# Sensor_Signal.net
KiCad netlist of a schematic drawn in Altium Designer
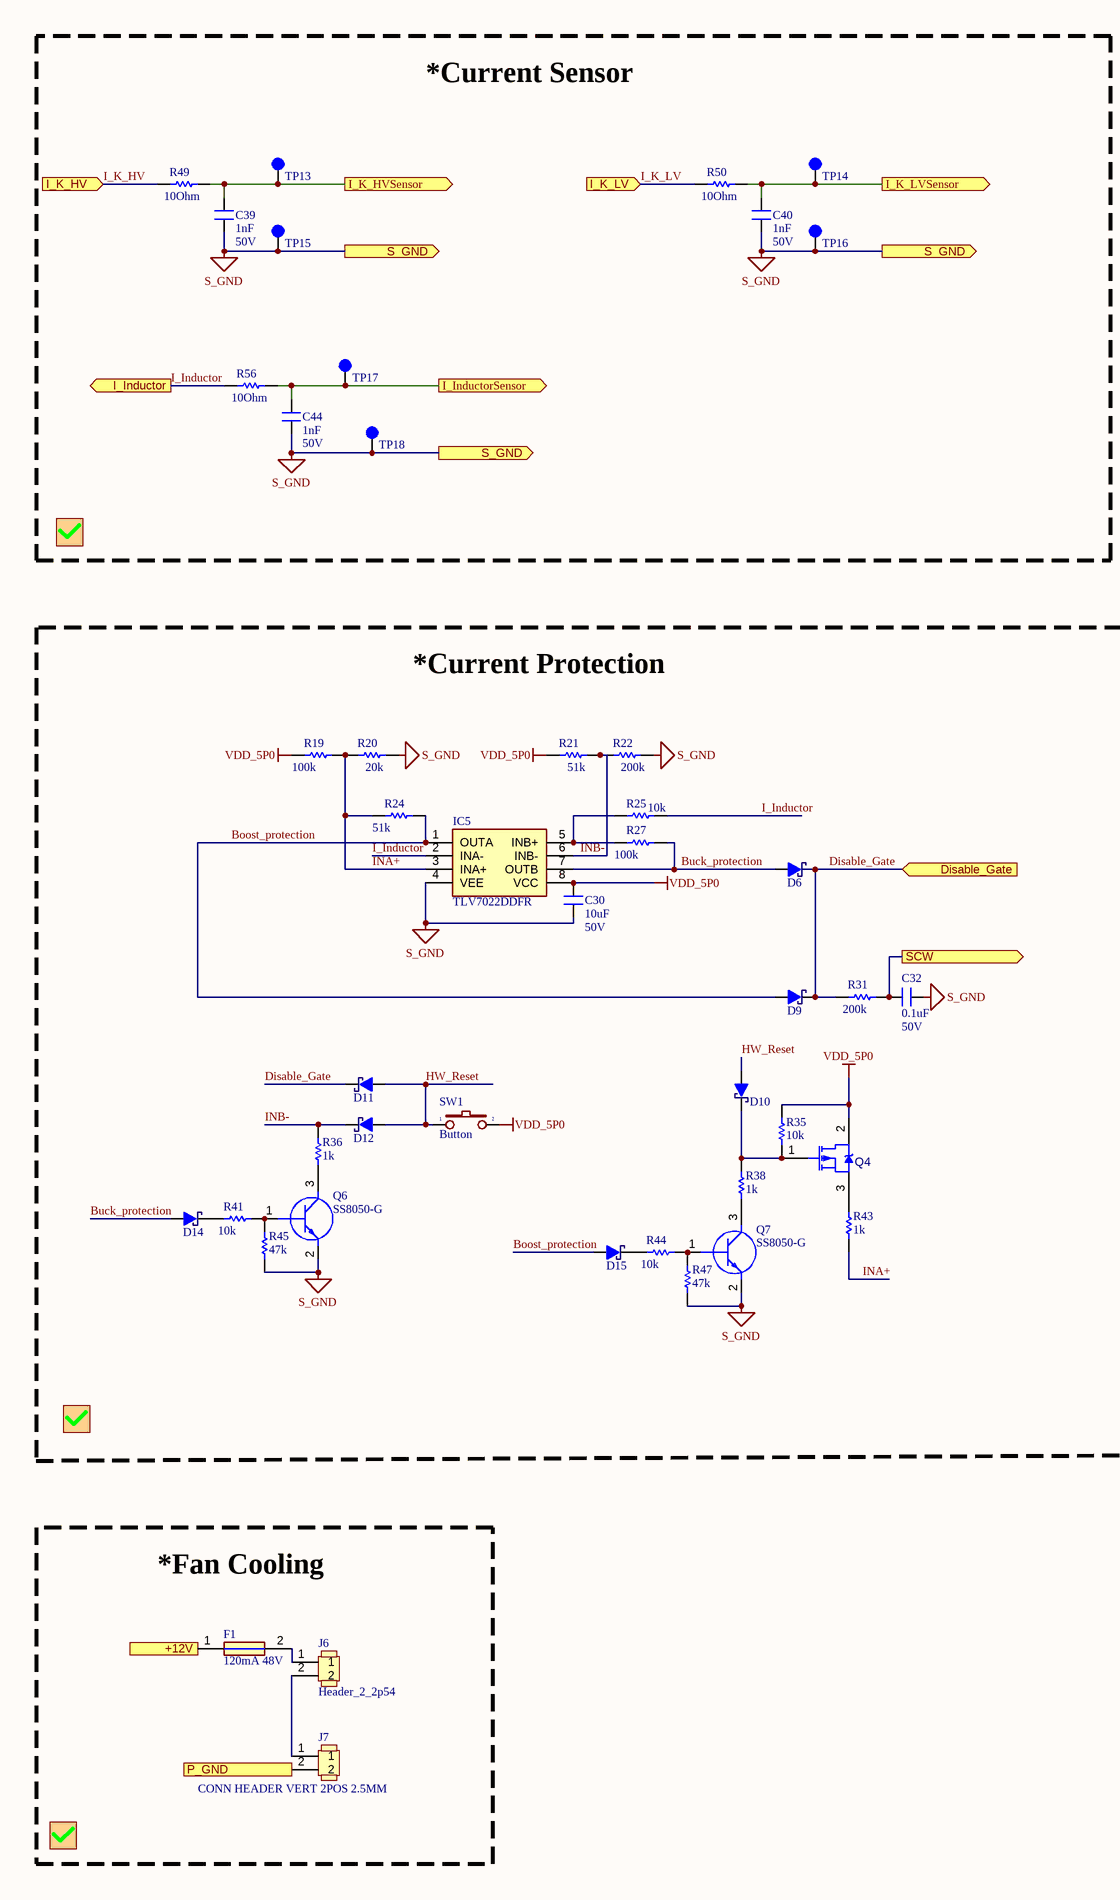
[diagram p0: Sensor Signal.SchDoc, left]
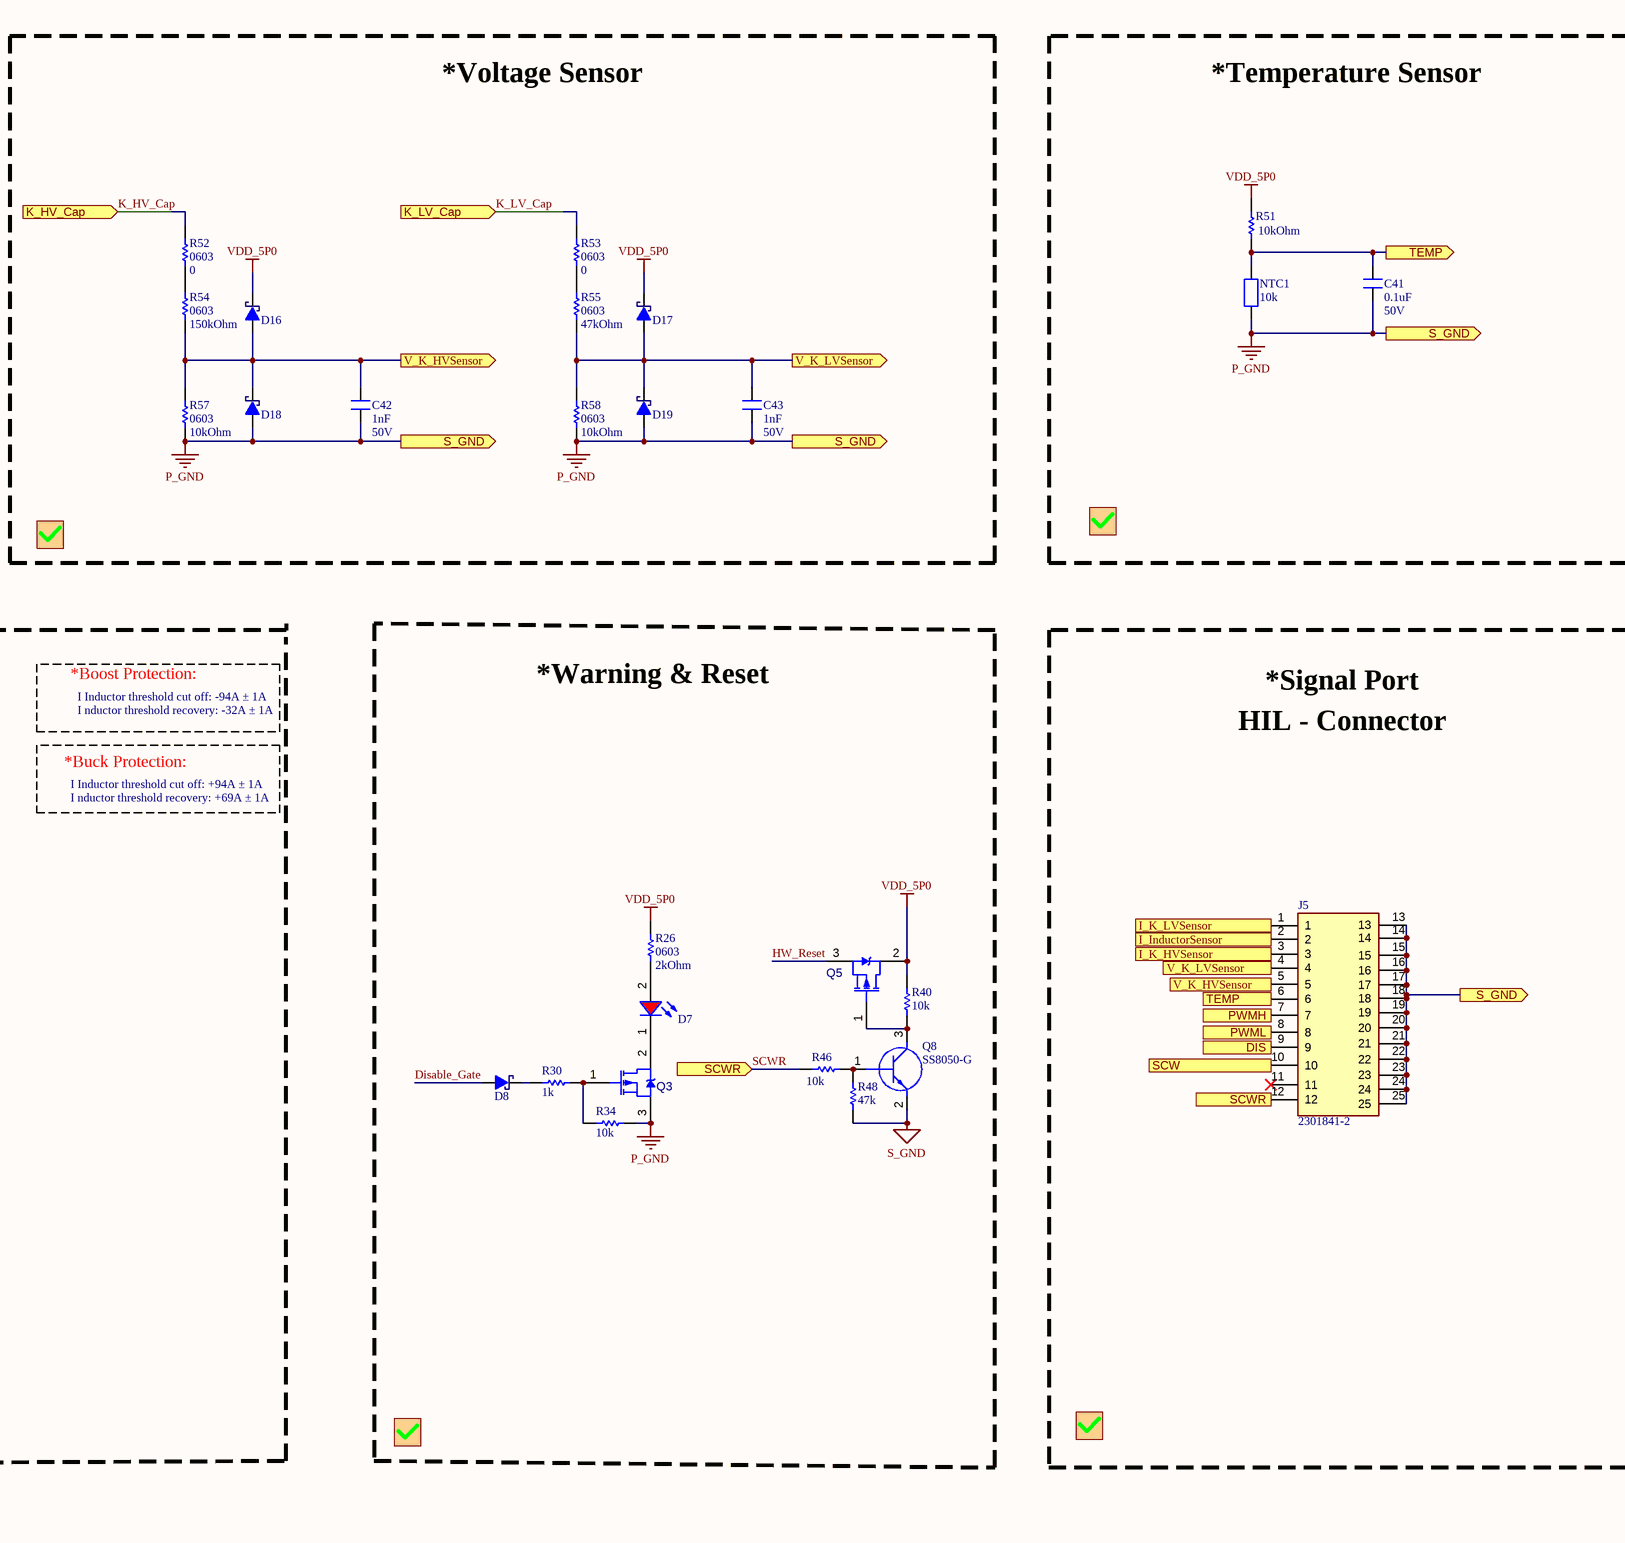
[diagram p1: Sensor Signal.SchDoc, right]

(export (version "E")
  (design (tool "Eeschema 10.0.6"))
  (components
    (comp (ref "C30")
      (value "10uF")
      (footprint "C_0603")
      (description "CAP CER 10UF 16V X5R 0805")
      (fields
        (field (name "MANUFACTURER") "Murata Electronics")
        (field (name "PART NUMBER") "CL21A106KOCLRNC")
        (field (name "ALTIUM_VALUE") "50V")
      )
      (libsource (lib "S1200_Capacitor") (part "Cap_Cer_0603_1nF_25V"))
    )
    (comp (ref "C32")
      (value "0.1uF")
      (footprint "C_0603")
      (description "CAP CER 0.1UF 16V X5R 0603")
      (fields
        (field (name "MANUFACTURER") "Murata Electronics")
        (field (name "PART NUMBER") "CL21A106KOCLRNC")
        (field (name "ALTIUM_VALUE") "50V")
      )
      (libsource (lib "S1200_Capacitor") (part "Cap_Cer_0603_1nF_25V"))
    )
    (comp (ref "C39")
      (value "1nF")
      (footprint "C_0603")
      (description "CAP CER 1nF 50V X7R 0603")
      (fields
        (field (name "MANUFACTURER") "Murata Electronics")
        (field (name "PART NUMBER") "GCM188R71E102KA37D")
        (field (name "ALTIUM_VALUE") "50V")
      )
      (libsource (lib "S1200_Capacitor") (part "Cap_Cer_0603_1nF_25V"))
    )
    (comp (ref "C40")
      (value "1nF")
      (footprint "C_0603")
      (description "CAP CER 1nF 50V X7R 0603")
      (fields
        (field (name "MANUFACTURER") "Murata Electronics")
        (field (name "PART NUMBER") "GCM188R71E102KA37D")
        (field (name "ALTIUM_VALUE") "50V")
      )
      (libsource (lib "S1200_Capacitor") (part "Cap_Cer_0603_1nF_25V"))
    )
    (comp (ref "C41")
      (value "0.1uF")
      (footprint "C_0603")
      (description "CAP CER 0.1uF 50V X7R 0603")
      (fields
        (field (name "MANUFACTURER") "Kemet")
        (field (name "PART NUMBER") "CL10C680JB81PNC")
        (field (name "ALTIUM_VALUE") "50V")
      )
      (libsource (lib "S1200_Capacitor") (part "Cap_Cer_0805_10pF"))
    )
    (comp (ref "C42")
      (value "1nF")
      (footprint "C_0603")
      (description "CAP CER 1nF 50V X7R 0603")
      (fields
        (field (name "MANUFACTURER") "Murata Electronics")
        (field (name "PART NUMBER") "GCM188R71E102KA37D")
        (field (name "ALTIUM_VALUE") "50V")
      )
      (libsource (lib "S1200_Capacitor") (part "Cap_Cer_0603_1nF_25V"))
    )
    (comp (ref "C43")
      (value "1nF")
      (footprint "C_0603")
      (description "CAP CER 1nF 50V X7R 0603")
      (fields
        (field (name "MANUFACTURER") "Murata Electronics")
        (field (name "PART NUMBER") "GCM188R71E102KA37D")
        (field (name "ALTIUM_VALUE") "50V")
      )
      (libsource (lib "S1200_Capacitor") (part "Cap_Cer_0603_1nF_25V"))
    )
    (comp (ref "C44")
      (value "1nF")
      (footprint "C_0603")
      (description "CAP CER 1nF 50V X7R 0603")
      (fields
        (field (name "MANUFACTURER") "Murata Electronics")
        (field (name "PART NUMBER") "GCM188R71E102KA37D")
        (field (name "ALTIUM_VALUE") "50V")
      )
      (libsource (lib "S1200_Capacitor") (part "Cap_Cer_0603_1nF_25V"))
    )
    (comp (ref "D6")
      (value "PMEG2010AEJ,115")
      (footprint "SOD323F")
      (description "DIODE SCHOTTKY 20V 1A SOD323F")
      (fields (field (name "MANUFACTURER") "Nexperia USA Inc.") (field (name "VOLTAGE") "20 V"))
      (libsource (lib "Motor Control SELEX MOTORS JSC") (part "PMEG2010AEJ,115"))
    )
    (comp (ref "D7")
      (value "LED-SMD")
      (footprint "SM-LED-0805-Red")
      (description "LED RED DIFFUSED 0805 SMD")
      (fields
        (field (name "MANUFACTURER") "OSRAM Opto Semiconductors Inc.")
        (field (name "PART NUMBER") "LS R976-NR-1")
      )
      (libsource (lib "Motor Control SELEX MOTORS JSC") (part "LED-SMD"))
    )
    (comp (ref "D8")
      (value "PMEG2010AEJ,115")
      (footprint "SOD323F")
      (description "DIODE SCHOTTKY 20V 1A SOD323F")
      (fields (field (name "MANUFACTURER") "Nexperia USA Inc.") (field (name "VOLTAGE") "20 V"))
      (libsource (lib "Motor Control SELEX MOTORS JSC") (part "PMEG2010AEJ,115"))
    )
    (comp (ref "D9")
      (value "PMEG2010AEJ,115")
      (footprint "SOD323F")
      (description "DIODE SCHOTTKY 20V 1A SOD323F")
      (fields (field (name "MANUFACTURER") "Nexperia USA Inc.") (field (name "VOLTAGE") "20 V"))
      (libsource (lib "Motor Control SELEX MOTORS JSC") (part "PMEG2010AEJ,115"))
    )
    (comp (ref "D10")
      (value "PMEG2010AEJ,115")
      (footprint "SOD323F")
      (description "DIODE SCHOTTKY 20V 1A SOD323F")
      (fields (field (name "MANUFACTURER") "Nexperia USA Inc.") (field (name "VOLTAGE") "20 V"))
      (libsource (lib "Motor Control SELEX MOTORS JSC") (part "PMEG2010AEJ,115"))
    )
    (comp (ref "D11")
      (value "PMEG2010AEJ,115")
      (footprint "SOD323F")
      (description "DIODE SCHOTTKY 20V 1A SOD323F")
      (fields (field (name "MANUFACTURER") "Nexperia USA Inc.") (field (name "VOLTAGE") "20 V"))
      (libsource (lib "Motor Control SELEX MOTORS JSC") (part "PMEG2010AEJ,115"))
    )
    (comp (ref "D12")
      (value "PMEG2010AEJ,115")
      (footprint "SOD323F")
      (description "DIODE SCHOTTKY 20V 1A SOD323F")
      (fields (field (name "MANUFACTURER") "Nexperia USA Inc.") (field (name "VOLTAGE") "20 V"))
      (libsource (lib "Motor Control SELEX MOTORS JSC") (part "PMEG2010AEJ,115"))
    )
    (comp (ref "D14")
      (value "PMEG2010AEJ,115")
      (footprint "SOD323F")
      (description "DIODE SCHOTTKY 20V 1A SOD323F")
      (fields (field (name "MANUFACTURER") "Nexperia USA Inc.") (field (name "VOLTAGE") "20 V"))
      (libsource (lib "Motor Control SELEX MOTORS JSC") (part "PMEG2010AEJ,115"))
    )
    (comp (ref "D15")
      (value "PMEG2010AEJ,115")
      (footprint "SOD323F")
      (description "DIODE SCHOTTKY 20V 1A SOD323F")
      (fields (field (name "MANUFACTURER") "Nexperia USA Inc.") (field (name "VOLTAGE") "20 V"))
      (libsource (lib "Motor Control SELEX MOTORS JSC") (part "PMEG2010AEJ,115"))
    )
    (comp (ref "D16")
      (value "PMEG2010AEJ,115")
      (footprint "SOD323F")
      (description "DIODE SCHOTTKY 20V 1A SOD323F")
      (fields (field (name "MANUFACTURER") "Nexperia USA Inc.") (field (name "VOLTAGE") "20 V"))
      (libsource (lib "Motor Control SELEX MOTORS JSC") (part "PMEG2010AEJ,115"))
    )
    (comp (ref "D17")
      (value "PMEG2010AEJ,115")
      (footprint "SOD323F")
      (description "DIODE SCHOTTKY 20V 1A SOD323F")
      (fields (field (name "MANUFACTURER") "Nexperia USA Inc.") (field (name "VOLTAGE") "20 V"))
      (libsource (lib "Motor Control SELEX MOTORS JSC") (part "PMEG2010AEJ,115"))
    )
    (comp (ref "D18")
      (value "PMEG2010AEJ,115")
      (footprint "SOD323F")
      (description "DIODE SCHOTTKY 20V 1A SOD323F")
      (fields (field (name "MANUFACTURER") "Nexperia USA Inc.") (field (name "VOLTAGE") "20 V"))
      (libsource (lib "Motor Control SELEX MOTORS JSC") (part "PMEG2010AEJ,115"))
    )
    (comp (ref "D19")
      (value "PMEG2010AEJ,115")
      (footprint "SOD323F")
      (description "DIODE SCHOTTKY 20V 1A SOD323F")
      (fields (field (name "MANUFACTURER") "Nexperia USA Inc.") (field (name "VOLTAGE") "20 V"))
      (libsource (lib "Motor Control SELEX MOTORS JSC") (part "PMEG2010AEJ,115"))
    )
    (comp (ref "F1")
      (value "120mA 48V")
      (footprint "Fuse-SMD-1206")
      (description "PTC 120mA 48V 2410")
      (fields (field (name "MANUFACTURER_PART_NUMBER") "0679L1000-01"))
      (libsource (lib "Tienanh") (part "Fuse"))
    )
    (comp (ref "IC5")
      (value "TLV7022DDFR")
      (footprint "SamacSys:SOT65P280X110-8N")
      (description "IC COMPARATOR 2 GEN PUR TSOT23-8")
      (fields (field (name "MOUSER PART NUMBER") "595-TLV7022DDFR"))
      (libsource (lib "*") (part "TLV7022DDFR"))
    )
    (comp (ref "J5")
      (value "2301841-2")
      (footprint "TE_2301841-2")
      (description "25 Position D-Sub Receptacle, Female Sockets Connector")
      (fields (field (name "MF") "TE Connectivity"))
      (libsource (lib "2301841-2") (part "2301841-2"))
    )
    (comp (ref "J6")
      (value "Header_2_2p54")
      (footprint "JUMP_1x2")
      (libsource (lib "S1900_Connector") (part "Header_2_2p54"))
    )
    (comp (ref "J7")
      (value "CONN HEADER VERT 2POS 2.5MM")
      (footprint "HEADER_2")
      (fields
        (field (name "MANUFACTURER") "JST Sales America Inc.")
        (field (name "PART NUMBER") "B2B-XH-A(LF)(SN)")
      )
      (libsource (lib "S1900_Connector") (part "Header_2"))
    )
    (comp (ref "NTC1")
      (value "10k")
      (footprint "NTC 0805")
      (description "THERMISTOR NTC 10KOHM 3940K 0805")
      (fields
        (field (name "MANUFACTURER") "Vishay Beyschlag/Draloric/BC Components")
        (field (name "PART NUMBER") "NTCS0805E3103JHT")
      )
      (libsource (lib "Tienanh") (part "NTC 10k 1%"))
    )
    (comp (ref "Q3")
      (value "IRLML6402TRPBF")
      (footprint "sot23-3")
      (description "MOSFET N-CH 20V 3.7A")
      (fields (field (name "MANUFACTURER") "INFINEON") (field (name "PART NUMBER") "DMP2160U-7"))
      (libsource (lib "Selex_Component_Lib") (part "IRLML6402TRPBF"))
    )
    (comp (ref "Q4")
      (value "IRLML6402TRPBF")
      (footprint "sot23-3")
      (description "MOSFET P-CH 20V 3.7A")
      (fields (field (name "MANUFACTURER") "INFINEON") (field (name "PART NUMBER") "IRLML6402"))
      (libsource (lib "Selex_Component_Lib") (part "IRLML6402TRPBF"))
    )
    (comp (ref "Q5")
      (value "IRLML6402TRPBF")
      (footprint "sot23-3")
      (description "MOSFET P-CH 20V 3.7A")
      (fields (field (name "MANUFACTURER") "INFINEON") (field (name "PART NUMBER") "IRLML6402"))
      (libsource (lib "Selex_Component_Lib") (part "IRLML6402TRPBF"))
    )
    (comp (ref "Q6")
      (value "SS8050-G")
      (footprint "sot23-3")
      (description "Transistor BJT NPN")
      (fields (field (name "MOUSER PART NUMBER") "750-SS8050-G"))
      (libsource (lib "*") (part "SS8050-G"))
    )
    (comp (ref "Q7")
      (value "SS8050-G")
      (footprint "sot23-3")
      (description "Transistor BJT NPN")
      (fields (field (name "MOUSER PART NUMBER") "750-SS8050-G"))
      (libsource (lib "*") (part "SS8050-G"))
    )
    (comp (ref "Q8")
      (value "SS8050-G")
      (footprint "sot23-3")
      (description "Transistor BJT NPN")
      (fields (field (name "MOUSER PART NUMBER") "750-SS8050-G"))
      (libsource (lib "*") (part "SS8050-G"))
    )
    (comp (ref "R19")
      (value "100k")
      (footprint "R_0603")
      (description "RES 100k OHM 1% 1/10W 0603")
      (fields (field (name "MANUFACTURER") "YAGEO") (field (name "PART NUMBER") "RC0603FR-071ML"))
      (libsource (lib "S1100_Resistor_FerriteBead") (part "Resistor_0603_1_MegaOhm_1%"))
    )
    (comp (ref "R20")
      (value "20k")
      (footprint "R_0603")
      (description "RES 20k OHM 1% 1/10W 0603")
      (fields (field (name "MANUFACTURER") "YAGEO") (field (name "PART NUMBER") "RC0603FR-071ML"))
      (libsource (lib "S1100_Resistor_FerriteBead") (part "Resistor_0603_1_MegaOhm_1%"))
    )
    (comp (ref "R21")
      (value "51k")
      (footprint "R_0603")
      (description "RES 51k OHM 1% 1/8W 0603")
      (fields
        (field (name "MANUFACTURER") "KOA Speer Electronics, Inc.")
        (field (name "PART NUMBER") "RT0603FRE07300KL")
      )
      (libsource (lib "S1100_Resistor_FerriteBead") (part "Resistor_0603_10Ohm 1%"))
    )
    (comp (ref "R22")
      (value "200k")
      (footprint "R_0603")
      (description "RES 200k OHM 1% 1/8W 0603")
      (fields
        (field (name "MANUFACTURER") "KOA Speer Electronics, Inc.")
        (field (name "PART NUMBER") "RT0603FRE07300KL")
      )
      (libsource (lib "S1100_Resistor_FerriteBead") (part "Resistor_0603_10Ohm 1%"))
    )
    (comp (ref "R24")
      (value "51k")
      (footprint "R_0603")
      (description "RES 51k OHM 1% 1/10W 0603")
      (fields (field (name "MANUFACTURER") "YAGEO") (field (name "PART NUMBER") "RC0603FR-071ML"))
      (libsource (lib "S1100_Resistor_FerriteBead") (part "Resistor_0603_1_MegaOhm_1%"))
    )
    (comp (ref "R25")
      (value "10k")
      (footprint "R_0603")
      (description "RES 10k OHM 1% 1/8W 0603")
      (fields
        (field (name "MANUFACTURER") "KOA Speer Electronics, Inc.")
        (field (name "PART NUMBER") "RNCF0805BTE250K")
      )
      (libsource (lib "S1100_Resistor_FerriteBead") (part "Resistor_0603_10Ohm 1%"))
    )
    (comp (ref "R26")
      (value "0603")
      (footprint "R_0603")
      (description "RES 2K OHM 1% 1/10W 0603")
      (fields
        (field (name "MANUFACTURER") "YAGEO")
        (field (name "PART NUMBER") "RC0603FR-074K7L")
        (field (name "ALTIUM_VALUE") "2kOhm")
      )
      (libsource (lib "S1100_Resistor_FerriteBead") (part "Resistor_0603_4.7kOhm"))
    )
    (comp (ref "R27")
      (value "100k")
      (footprint "R_0603")
      (description "RES 100k OHM 1% 1/10W 0603")
      (fields (field (name "MANUFACTURER") "YAGEO") (field (name "PART NUMBER") "RC0603FR-071ML"))
      (libsource (lib "S1100_Resistor_FerriteBead") (part "Resistor_0603_1_MegaOhm_1%"))
    )
    (comp (ref "R30")
      (value "1k")
      (footprint "R_0603")
      (description "RES 200K OHM 1% 1/10W 0603")
      (fields (field (name "MANUFACTURER") "YAGEO") (field (name "PART NUMBER") "RC0603FR-13200KL"))
      (libsource (lib "S1100_Resistor_FerriteBead") (part "Resistor_0603_10Ohm 1%"))
    )
    (comp (ref "R31")
      (value "200k")
      (footprint "R_0603")
      (description "RES 200K OHM 1% 1/10W 0603")
      (fields (field (name "MANUFACTURER") "YAGEO") (field (name "PART NUMBER") "RC0603FR-13200KL"))
      (libsource (lib "S1100_Resistor_FerriteBead") (part "Resistor_0603_10Ohm 1%"))
    )
    (comp (ref "R34")
      (value "10k")
      (footprint "R_0603")
      (description "RES 10K OHM 1% 1/10W 0603")
      (fields (field (name "MANUFACTURER") "YAGEO") (field (name "PART NUMBER") "RC0603FR-13200KL"))
      (libsource (lib "S1100_Resistor_FerriteBead") (part "Resistor_0603_10Ohm 1%"))
    )
    (comp (ref "R35")
      (value "10k")
      (footprint "R_0603")
      (description "RES 47K OHM 1% 1/10W 0603")
      (fields (field (name "MANUFACTURER") "YAGEO") (field (name "PART NUMBER") "RC0603FR-13200KL"))
      (libsource (lib "S1100_Resistor_FerriteBead") (part "Resistor_0603_10Ohm 1%"))
    )
    (comp (ref "R36")
      (value "1k")
      (footprint "R_0603")
      (description "RES 1K OHM 1% 1/10W 0603")
      (fields (field (name "MANUFACTURER") "YAGEO") (field (name "PART NUMBER") "RC0603FR-13200KL"))
      (libsource (lib "S1100_Resistor_FerriteBead") (part "Resistor_0603_10Ohm 1%"))
    )
    (comp (ref "R38")
      (value "1k")
      (footprint "R_0603")
      (description "RES 200K OHM 1% 1/10W 0603")
      (fields (field (name "MANUFACTURER") "YAGEO") (field (name "PART NUMBER") "RC0603FR-13200KL"))
      (libsource (lib "S1100_Resistor_FerriteBead") (part "Resistor_0603_10Ohm 1%"))
    )
    (comp (ref "R40")
      (value "10k")
      (footprint "R_0603")
      (description "RES 47K OHM 1% 1/10W 0603")
      (fields (field (name "MANUFACTURER") "YAGEO") (field (name "PART NUMBER") "RC0603FR-13200KL"))
      (libsource (lib "S1100_Resistor_FerriteBead") (part "Resistor_0603_10Ohm 1%"))
    )
    (comp (ref "R41")
      (value "10k")
      (footprint "R_0603")
      (description "RES 10K OHM 1% 1/10W 0603")
      (fields (field (name "MANUFACTURER") "YAGEO") (field (name "PART NUMBER") "RC0603FR-13200KL"))
      (libsource (lib "S1100_Resistor_FerriteBead") (part "Resistor_0603_10Ohm 1%"))
    )
    (comp (ref "R43")
      (value "1k")
      (footprint "R_0603")
      (description "RES 200K OHM 1% 1/10W 0603")
      (fields (field (name "MANUFACTURER") "YAGEO") (field (name "PART NUMBER") "RC0603FR-13200KL"))
      (libsource (lib "S1100_Resistor_FerriteBead") (part "Resistor_0603_10Ohm 1%"))
    )
    (comp (ref "R44")
      (value "10k")
      (footprint "R_0603")
      (description "RES 10K OHM 1% 1/10W 0603")
      (fields (field (name "MANUFACTURER") "YAGEO") (field (name "PART NUMBER") "RC0603FR-13200KL"))
      (libsource (lib "S1100_Resistor_FerriteBead") (part "Resistor_0603_10Ohm 1%"))
    )
    (comp (ref "R45")
      (value "47k")
      (footprint "R_0603")
      (description "RES 47K OHM 1% 1/10W 0603")
      (fields (field (name "MANUFACTURER") "YAGEO") (field (name "PART NUMBER") "RC0603FR-13200KL"))
      (libsource (lib "S1100_Resistor_FerriteBead") (part "Resistor_0603_10Ohm 1%"))
    )
    (comp (ref "R46")
      (value "10k")
      (footprint "R_0603")
      (description "RES 10K OHM 1% 1/10W 0603")
      (fields (field (name "MANUFACTURER") "YAGEO") (field (name "PART NUMBER") "RC0603FR-13200KL"))
      (libsource (lib "S1100_Resistor_FerriteBead") (part "Resistor_0603_10Ohm 1%"))
    )
    (comp (ref "R47")
      (value "47k")
      (footprint "R_0603")
      (description "RES 47K OHM 1% 1/10W 0603")
      (fields (field (name "MANUFACTURER") "YAGEO") (field (name "PART NUMBER") "RC0603FR-13200KL"))
      (libsource (lib "S1100_Resistor_FerriteBead") (part "Resistor_0603_10Ohm 1%"))
    )
    (comp (ref "R48")
      (value "47k")
      (footprint "R_0603")
      (description "RES 47K OHM 1% 1/10W 0603")
      (fields (field (name "MANUFACTURER") "YAGEO") (field (name "PART NUMBER") "RC0603FR-13200KL"))
      (libsource (lib "S1100_Resistor_FerriteBead") (part "Resistor_0603_10Ohm 1%"))
    )
    (comp (ref "R49")
      (value "10Ohm")
      (footprint "R_0603")
      (description "RES 10 OHM 1% 1/10W 0603")
      (fields (field (name "MANUFACTURER") "Vishay Dale") (field (name "PART NUMBER") "CRCW06031K00FKTA"))
      (libsource (lib "S1100_Resistor_FerriteBead") (part "Resistor_0603_1kOhm"))
    )
    (comp (ref "R50")
      (value "10Ohm")
      (footprint "R_0603")
      (description "RES 10 OHM 1% 1/10W 0603")
      (fields (field (name "MANUFACTURER") "Vishay Dale") (field (name "PART NUMBER") "CRCW06031K00FKTA"))
      (libsource (lib "S1100_Resistor_FerriteBead") (part "Resistor_0603_1kOhm"))
    )
    (comp (ref "R51")
      (value "10kOhm")
      (footprint "R_0603")
      (description "RES 10K OHM 1% 1/10W 0603")
      (fields (field (name "MANUFACTURER") "YAGEO") (field (name "PART NUMBER") "RC0603FR-7W10KL"))
      (libsource (lib "S1100_Resistor_FerriteBead") (part "Resistor_0603_10kOhm 1%"))
    )
    (comp (ref "R52")
      (value "0603")
      (footprint "R_0603")
      (description "RES SMD 0 OHM 1% 1/8W 0603")
      (fields
        (field (name "MANUFACTURER") "Vishay Beyschlag/Draloric/BC Components")
        (field (name "PART NUMBER") "MCT06030C2203FP500")
        (field (name "ALTIUM_VALUE") "0")
      )
      (libsource (lib "S1100_Resistor_FerriteBead") (part "Resistor_0603_220kOhm"))
    )
    (comp (ref "R53")
      (value "0603")
      (footprint "R_0603")
      (description "RES SMD 0 OHM 1% 1/8W 0603")
      (fields
        (field (name "MANUFACTURER") "Vishay Beyschlag/Draloric/BC Components")
        (field (name "PART NUMBER") "MCT06030C2203FP500")
        (field (name "ALTIUM_VALUE") "0")
      )
      (libsource (lib "S1100_Resistor_FerriteBead") (part "Resistor_0603_220kOhm"))
    )
    (comp (ref "R54")
      (value "0603")
      (footprint "R_0603")
      (description "RES SMD 150K OHM 1% 1/8W 0603")
      (fields
        (field (name "MANUFACTURER") "Vishay Beyschlag/Draloric/BC Components")
        (field (name "PART NUMBER") "MCT06030C2203FP500")
        (field (name "ALTIUM_VALUE") "150kOhm")
      )
      (libsource (lib "S1100_Resistor_FerriteBead") (part "Resistor_0603_220kOhm"))
    )
    (comp (ref "R55")
      (value "0603")
      (footprint "R_0603")
      (description "RES SMD 150K OHM 1% 1/8W 0603")
      (fields
        (field (name "MANUFACTURER") "Vishay Beyschlag/Draloric/BC Components")
        (field (name "PART NUMBER") "MCT06030C2203FP500")
        (field (name "ALTIUM_VALUE") "47kOhm")
      )
      (libsource (lib "S1100_Resistor_FerriteBead") (part "Resistor_0603_220kOhm"))
    )
    (comp (ref "R56")
      (value "10Ohm")
      (footprint "R_0603")
      (description "RES 10 OHM 1% 1/10W 0603")
      (fields (field (name "MANUFACTURER") "Vishay Dale") (field (name "PART NUMBER") "CRCW06031K00FKTA"))
      (libsource (lib "S1100_Resistor_FerriteBead") (part "Resistor_0603_1kOhm"))
    )
    (comp (ref "R57")
      (value "0603")
      (footprint "R_0603")
      (description "RES SMD 220K OHM 1% 1/8W 0603")
      (fields
        (field (name "MANUFACTURER") "Vishay Beyschlag/Draloric/BC Components")
        (field (name "PART NUMBER") "MCT06030C2203FP500")
        (field (name "ALTIUM_VALUE") "10kOhm")
      )
      (libsource (lib "S1100_Resistor_FerriteBead") (part "Resistor_0603_220kOhm"))
    )
    (comp (ref "R58")
      (value "0603")
      (footprint "R_0603")
      (description "RES SMD 220K OHM 1% 1/8W 0603")
      (fields
        (field (name "MANUFACTURER") "Vishay Beyschlag/Draloric/BC Components")
        (field (name "PART NUMBER") "MCT06030C2203FP500")
        (field (name "ALTIUM_VALUE") "10kOhm")
      )
      (libsource (lib "S1100_Resistor_FerriteBead") (part "Resistor_0603_220kOhm"))
    )
    (comp (ref "SW1")
      (value "Button")
      (footprint "BUTTON_2P_SMD")
      (description "Nút nhấn 2 chân dán 3x6x2.5mm")
      (libsource (lib "BMS v2.1") (part "SW2"))
    )
    (comp (ref "TP13")
      (value "Test Point")
      (footprint "TP_1mm_through_hole")
      (description "PC TEST POINT COMPACT RED")
      (fields (field (name "PART NUMBER") "5005") (field (name "MANUFACTURER") "Keystone Electronics"))
      (libsource (lib "Tienanh") (part "Test Point"))
    )
    (comp (ref "TP14")
      (value "Test Point")
      (footprint "TP_1mm_through_hole")
      (description "PC TEST POINT COMPACT RED")
      (fields (field (name "PART NUMBER") "5005") (field (name "MANUFACTURER") "Keystone Electronics"))
      (libsource (lib "Tienanh") (part "Test Point"))
    )
    (comp (ref "TP15")
      (value "Test Point")
      (footprint "TP_1mm_through_hole")
      (description "PC TEST POINT COMPACT RED")
      (fields (field (name "PART NUMBER") "5005") (field (name "MANUFACTURER") "Keystone Electronics"))
      (libsource (lib "Tienanh") (part "Test Point"))
    )
    (comp (ref "TP16")
      (value "Test Point")
      (footprint "TP_1mm_through_hole")
      (description "PC TEST POINT COMPACT RED")
      (fields (field (name "PART NUMBER") "5005") (field (name "MANUFACTURER") "Keystone Electronics"))
      (libsource (lib "Tienanh") (part "Test Point"))
    )
    (comp (ref "TP17")
      (value "Test Point")
      (footprint "TP_1mm_through_hole")
      (description "PC TEST POINT COMPACT RED")
      (fields (field (name "PART NUMBER") "5005") (field (name "MANUFACTURER") "Keystone Electronics"))
      (libsource (lib "Tienanh") (part "Test Point"))
    )
    (comp (ref "TP18")
      (value "Test Point")
      (footprint "TP_1mm_through_hole")
      (description "PC TEST POINT COMPACT RED")
      (fields (field (name "PART NUMBER") "5005") (field (name "MANUFACTURER") "Keystone Electronics"))
      (libsource (lib "Tienanh") (part "Test Point"))
    )
  )
  (nets
    (net (code "1") (name "/+12V") (class "Default")
      (node (ref "F1") (pin "1") (pinfunction "1_1") (pintype "passive"))
    )
    (net (code "2") (name "/Boost_protection") (class "Default")
      (node (ref "D15") (pin "1") (pinfunction "1_1") (pintype "passive"))
      (node (ref "D9") (pin "1") (pinfunction "1_1") (pintype "passive"))
      (node (ref "IC5") (pin "1") (pinfunction "OUTA_1") (pintype "passive"))
      (node (ref "R24") (pin "2") (pinfunction "2_2") (pintype "passive"))
    )
    (net (code "3") (name "/Buck_protection") (class "Default")
      (node (ref "D14") (pin "1") (pinfunction "1_1") (pintype "passive"))
      (node (ref "D6") (pin "1") (pinfunction "1_1") (pintype "passive"))
      (node (ref "IC5") (pin "7") (pinfunction "OUTB_7") (pintype "passive"))
      (node (ref "R27") (pin "2") (pinfunction "2_2") (pintype "passive"))
    )
    (net (code "4") (name "/DIS") (class "Default")
      (node (ref "J5") (pin "9") (pinfunction "9_9") (pintype "passive"))
    )
    (net (code "5") (name "/Disable_Gate") (class "Default")
      (node (ref "D11") (pin "2") (pinfunction "2_2") (pintype "passive"))
      (node (ref "D6") (pin "2") (pinfunction "2_2") (pintype "passive"))
      (node (ref "D8") (pin "1") (pinfunction "1_1") (pintype "passive"))
      (node (ref "D9") (pin "2") (pinfunction "2_2") (pintype "passive"))
      (node (ref "R31") (pin "1") (pinfunction "1_1") (pintype "passive"))
    )
    (net (code "6") (name "/HW_Reset") (class "Default")
      (node (ref "D10") (pin "1") (pinfunction "1_1") (pintype "passive"))
      (node (ref "D11") (pin "1") (pinfunction "1_1") (pintype "passive"))
      (node (ref "D12") (pin "1") (pinfunction "1_1") (pintype "passive"))
      (node (ref "Q5") (pin "3") (pinfunction "S_3") (pintype "passive"))
      (node (ref "SW1") (pin "1") (pinfunction "1_1") (pintype "passive"))
    )
    (net (code "7") (name "/INA+") (class "Default")
      (node (ref "IC5") (pin "3") (pinfunction "INA+_3") (pintype "passive"))
      (node (ref "R19") (pin "2") (pinfunction "2_2") (pintype "passive"))
      (node (ref "R20") (pin "1") (pinfunction "1_1") (pintype "passive"))
      (node (ref "R24") (pin "1") (pinfunction "1_1") (pintype "passive"))
      (node (ref "R43") (pin "1") (pinfunction "1_1") (pintype "passive"))
    )
    (net (code "8") (name "/INB-") (class "Default")
      (node (ref "D12") (pin "2") (pinfunction "2_2") (pintype "passive"))
      (node (ref "IC5") (pin "6") (pinfunction "INB-_6") (pintype "passive"))
      (node (ref "R21") (pin "2") (pinfunction "2_2") (pintype "passive"))
      (node (ref "R22") (pin "1") (pinfunction "1_1") (pintype "passive"))
      (node (ref "R36") (pin "2") (pinfunction "2_2") (pintype "passive"))
    )
    (net (code "9") (name "/I_Inductor") (class "Default")
      (node (ref "IC5") (pin "2") (pinfunction "INA-_2") (pintype "passive"))
      (node (ref "R25") (pin "2") (pinfunction "2_2") (pintype "passive"))
      (node (ref "R56") (pin "1") (pinfunction "1_1") (pintype "passive"))
    )
    (net (code "10") (name "/I_InductorSensor") (class "Default")
      (node (ref "C44") (pin "2") (pinfunction "2_2") (pintype "passive"))
      (node (ref "J5") (pin "2") (pinfunction "2_2") (pintype "passive"))
      (node (ref "R56") (pin "2") (pinfunction "2_2") (pintype "passive"))
      (node (ref "TP17") (pin "1") (pinfunction "B_1") (pintype "passive"))
    )
    (net (code "11") (name "/I_K_HV") (class "Default")
      (node (ref "R49") (pin "1") (pinfunction "1_1") (pintype "passive"))
    )
    (net (code "12") (name "/I_K_HVSensor") (class "Default")
      (node (ref "C39") (pin "2") (pinfunction "2_2") (pintype "passive"))
      (node (ref "J5") (pin "3") (pinfunction "3_3") (pintype "passive"))
      (node (ref "R49") (pin "2") (pinfunction "2_2") (pintype "passive"))
      (node (ref "TP13") (pin "1") (pinfunction "B_1") (pintype "passive"))
    )
    (net (code "13") (name "/I_K_LV") (class "Default")
      (node (ref "R50") (pin "1") (pinfunction "1_1") (pintype "passive"))
    )
    (net (code "14") (name "/I_K_LVSensor") (class "Default")
      (node (ref "C40") (pin "2") (pinfunction "2_2") (pintype "passive"))
      (node (ref "J5") (pin "1") (pinfunction "1_1") (pintype "passive"))
      (node (ref "R50") (pin "2") (pinfunction "2_2") (pintype "passive"))
      (node (ref "TP14") (pin "1") (pinfunction "B_1") (pintype "passive"))
    )
    (net (code "15") (name "/K_HV_Cap") (class "Default")
      (node (ref "R52") (pin "2") (pinfunction "2_2") (pintype "passive"))
    )
    (net (code "16") (name "/K_LV_Cap") (class "Default")
      (node (ref "R53") (pin "2") (pinfunction "2_2") (pintype "passive"))
    )
    (net (code "17") (name "/PWMH") (class "Default")
      (node (ref "J5") (pin "7") (pinfunction "7_7") (pintype "passive"))
    )
    (net (code "18") (name "/PWML") (class "Default")
      (node (ref "J5") (pin "8") (pinfunction "8_8") (pintype "passive"))
    )
    (net (code "19") (name "/SCW") (class "Default")
      (node (ref "C32") (pin "1") (pinfunction "1_1") (pintype "passive"))
      (node (ref "J5") (pin "10") (pinfunction "10_10") (pintype "passive"))
      (node (ref "R31") (pin "2") (pinfunction "2_2") (pintype "passive"))
    )
    (net (code "20") (name "/SCWR") (class "Default")
      (node (ref "J5") (pin "12") (pinfunction "12_12") (pintype "passive"))
      (node (ref "R46") (pin "1") (pinfunction "1_1") (pintype "passive"))
    )
    (net (code "21") (name "/TEMP") (class "Default")
      (node (ref "C41") (pin "2") (pinfunction "2_2") (pintype "passive"))
      (node (ref "J5") (pin "6") (pinfunction "6_6") (pintype "passive"))
      (node (ref "NTC1") (pin "2") (pinfunction "2_2") (pintype "passive"))
      (node (ref "R51") (pin "1") (pinfunction "1_1") (pintype "passive"))
    )
    (net (code "22") (name "/V_K_HVSensor") (class "Default")
      (node (ref "C42") (pin "2") (pinfunction "2_2") (pintype "passive"))
      (node (ref "D16") (pin "1") (pinfunction "1_1") (pintype "passive"))
      (node (ref "D18") (pin "2") (pinfunction "2_2") (pintype "passive"))
      (node (ref "J5") (pin "5") (pinfunction "5_5") (pintype "passive"))
      (node (ref "R54") (pin "1") (pinfunction "1_1") (pintype "passive"))
      (node (ref "R57") (pin "2") (pinfunction "2_2") (pintype "passive"))
    )
    (net (code "23") (name "/V_K_LVSensor") (class "Default")
      (node (ref "C43") (pin "2") (pinfunction "2_2") (pintype "passive"))
      (node (ref "D17") (pin "1") (pinfunction "1_1") (pintype "passive"))
      (node (ref "D19") (pin "2") (pinfunction "2_2") (pintype "passive"))
      (node (ref "J5") (pin "4") (pinfunction "4_4") (pintype "passive"))
      (node (ref "R55") (pin "1") (pinfunction "1_1") (pintype "passive"))
      (node (ref "R58") (pin "2") (pinfunction "2_2") (pintype "passive"))
    )
    (net (code "24") (name "Net-(D7-A)") (class "Default")
      (node (ref "D7") (pin "2") (pinfunction "A_2") (pintype "passive"))
      (node (ref "R26") (pin "1") (pinfunction "1_1") (pintype "passive"))
    )
    (net (code "25") (name "Net-(D7-K)") (class "Default")
      (node (ref "D7") (pin "1") (pinfunction "K_1") (pintype "passive"))
      (node (ref "Q3") (pin "2") (pinfunction "D_2") (pintype "passive"))
    )
    (net (code "26") (name "Net-(D8-Pad2)") (class "Default")
      (node (ref "D8") (pin "2") (pinfunction "2_2") (pintype "passive"))
      (node (ref "R30") (pin "2") (pinfunction "2_2") (pintype "passive"))
    )
    (net (code "27") (name "Net-(D14-Pad2)") (class "Default")
      (node (ref "D14") (pin "2") (pinfunction "2_2") (pintype "passive"))
      (node (ref "R41") (pin "1") (pinfunction "1_1") (pintype "passive"))
    )
    (net (code "28") (name "Net-(D15-Pad2)") (class "Default")
      (node (ref "D15") (pin "2") (pinfunction "2_2") (pintype "passive"))
      (node (ref "R44") (pin "1") (pinfunction "1_1") (pintype "passive"))
    )
    (net (code "29") (name "Net-(F1-Pad2)") (class "Default")
      (node (ref "F1") (pin "2") (pinfunction "2_2") (pintype "passive"))
      (node (ref "J6") (pin "1") (pinfunction "1_1") (pintype "passive"))
    )
    (net (code "30") (name "Net-(IC5-INB+)") (class "Default")
      (node (ref "IC5") (pin "5") (pinfunction "INB+_5") (pintype "passive"))
      (node (ref "R25") (pin "1") (pinfunction "1_1") (pintype "passive"))
      (node (ref "R27") (pin "1") (pinfunction "1_1") (pintype "passive"))
    )
    (net (code "31") (name "Net-(J6-Pad2)") (class "Default")
      (node (ref "J6") (pin "2") (pinfunction "2_2") (pintype "passive"))
      (node (ref "J7") (pin "1") (pinfunction "1_1") (pintype "passive"))
    )
    (net (code "32") (name "Net-(Q3-G)") (class "Default")
      (node (ref "Q3") (pin "1") (pinfunction "G_1") (pintype "passive"))
      (node (ref "R30") (pin "1") (pinfunction "1_1") (pintype "passive"))
      (node (ref "R34") (pin "1") (pinfunction "1_1") (pintype "passive"))
    )
    (net (code "33") (name "Net-(Q4-G)") (class "Default")
      (node (ref "D10") (pin "2") (pinfunction "2_2") (pintype "passive"))
      (node (ref "Q4") (pin "1") (pinfunction "G_1") (pintype "passive"))
      (node (ref "R35") (pin "1") (pinfunction "1_1") (pintype "passive"))
      (node (ref "R38") (pin "2") (pinfunction "2_2") (pintype "passive"))
    )
    (net (code "34") (name "Net-(Q4-S)") (class "Default")
      (node (ref "Q4") (pin "3") (pinfunction "S_3") (pintype "passive"))
      (node (ref "R43") (pin "2") (pinfunction "2_2") (pintype "passive"))
    )
    (net (code "35") (name "Net-(Q5-G)") (class "Default")
      (node (ref "Q5") (pin "1") (pinfunction "G_1") (pintype "passive"))
      (node (ref "Q8") (pin "3") (pinfunction "C_3") (pintype "passive"))
      (node (ref "R40") (pin "1") (pinfunction "1_1") (pintype "passive"))
    )
    (net (code "36") (name "Net-(Q6-B)") (class "Default")
      (node (ref "Q6") (pin "1") (pinfunction "B_1") (pintype "passive"))
      (node (ref "R41") (pin "2") (pinfunction "2_2") (pintype "passive"))
      (node (ref "R45") (pin "2") (pinfunction "2_2") (pintype "passive"))
    )
    (net (code "37") (name "Net-(Q6-C)") (class "Default")
      (node (ref "Q6") (pin "3") (pinfunction "C_3") (pintype "passive"))
      (node (ref "R36") (pin "1") (pinfunction "1_1") (pintype "passive"))
    )
    (net (code "38") (name "Net-(Q7-B)") (class "Default")
      (node (ref "Q7") (pin "1") (pinfunction "B_1") (pintype "passive"))
      (node (ref "R44") (pin "2") (pinfunction "2_2") (pintype "passive"))
      (node (ref "R47") (pin "2") (pinfunction "2_2") (pintype "passive"))
    )
    (net (code "39") (name "Net-(Q7-C)") (class "Default")
      (node (ref "Q7") (pin "3") (pinfunction "C_3") (pintype "passive"))
      (node (ref "R38") (pin "1") (pinfunction "1_1") (pintype "passive"))
    )
    (net (code "40") (name "Net-(Q8-B)") (class "Default")
      (node (ref "Q8") (pin "1") (pinfunction "B_1") (pintype "passive"))
      (node (ref "R46") (pin "2") (pinfunction "2_2") (pintype "passive"))
      (node (ref "R48") (pin "2") (pinfunction "2_2") (pintype "passive"))
    )
    (net (code "41") (name "Net-(R52-Pad1)") (class "Default")
      (node (ref "R52") (pin "1") (pinfunction "1_1") (pintype "passive"))
      (node (ref "R54") (pin "2") (pinfunction "2_2") (pintype "passive"))
    )
    (net (code "42") (name "Net-(R53-Pad1)") (class "Default")
      (node (ref "R53") (pin "1") (pinfunction "1_1") (pintype "passive"))
      (node (ref "R55") (pin "2") (pinfunction "2_2") (pintype "passive"))
    )
    (net (code "43") (name "P_GND") (class "Default")
      (node (ref "C30") (pin "1") (pinfunction "1_1") (pintype "passive"))
      (node (ref "C32") (pin "2") (pinfunction "2_2") (pintype "passive"))
      (node (ref "C39") (pin "1") (pinfunction "1_1") (pintype "passive"))
      (node (ref "C40") (pin "1") (pinfunction "1_1") (pintype "passive"))
      (node (ref "C41") (pin "1") (pinfunction "1_1") (pintype "passive"))
      (node (ref "C42") (pin "1") (pinfunction "1_1") (pintype "passive"))
      (node (ref "C43") (pin "1") (pinfunction "1_1") (pintype "passive"))
      (node (ref "C44") (pin "1") (pinfunction "1_1") (pintype "passive"))
      (node (ref "D18") (pin "1") (pinfunction "1_1") (pintype "passive"))
      (node (ref "D19") (pin "1") (pinfunction "1_1") (pintype "passive"))
      (node (ref "IC5") (pin "4") (pinfunction "VEE_4") (pintype "passive"))
      (node (ref "J5") (pin "13") (pinfunction "13_13") (pintype "passive"))
      (node (ref "J5") (pin "14") (pinfunction "14_14") (pintype "passive"))
      (node (ref "J5") (pin "15") (pinfunction "15_15") (pintype "passive"))
      (node (ref "J5") (pin "16") (pinfunction "16_16") (pintype "passive"))
      (node (ref "J5") (pin "17") (pinfunction "17_17") (pintype "passive"))
      (node (ref "J5") (pin "18") (pinfunction "18_18") (pintype "passive"))
      (node (ref "J5") (pin "19") (pinfunction "19_19") (pintype "passive"))
      (node (ref "J5") (pin "20") (pinfunction "20_20") (pintype "passive"))
      (node (ref "J5") (pin "21") (pinfunction "21_21") (pintype "passive"))
      (node (ref "J5") (pin "22") (pinfunction "22_22") (pintype "passive"))
      (node (ref "J5") (pin "23") (pinfunction "23_23") (pintype "passive"))
      (node (ref "J5") (pin "24") (pinfunction "24_24") (pintype "passive"))
      (node (ref "J5") (pin "25") (pinfunction "25_25") (pintype "passive"))
      (node (ref "J7") (pin "2") (pinfunction "2_2") (pintype "passive"))
      (node (ref "NTC1") (pin "1") (pinfunction "1_1") (pintype "passive"))
      (node (ref "Q3") (pin "3") (pinfunction "S_3") (pintype "passive"))
      (node (ref "Q6") (pin "2") (pinfunction "E_2") (pintype "passive"))
      (node (ref "Q7") (pin "2") (pinfunction "E_2") (pintype "passive"))
      (node (ref "Q8") (pin "2") (pinfunction "E_2") (pintype "passive"))
      (node (ref "R20") (pin "2") (pinfunction "2_2") (pintype "passive"))
      (node (ref "R22") (pin "2") (pinfunction "2_2") (pintype "passive"))
      (node (ref "R34") (pin "2") (pinfunction "2_2") (pintype "passive"))
      (node (ref "R45") (pin "1") (pinfunction "1_1") (pintype "passive"))
      (node (ref "R47") (pin "1") (pinfunction "1_1") (pintype "passive"))
      (node (ref "R48") (pin "1") (pinfunction "1_1") (pintype "passive"))
      (node (ref "R57") (pin "1") (pinfunction "1_1") (pintype "passive"))
      (node (ref "R58") (pin "1") (pinfunction "1_1") (pintype "passive"))
      (node (ref "TP15") (pin "1") (pinfunction "B_1") (pintype "passive"))
      (node (ref "TP16") (pin "1") (pinfunction "B_1") (pintype "passive"))
      (node (ref "TP18") (pin "1") (pinfunction "B_1") (pintype "passive"))
    )
    (net (code "44") (name "VDD_5P0") (class "Default")
      (node (ref "C30") (pin "2") (pinfunction "2_2") (pintype "passive"))
      (node (ref "D16") (pin "2") (pinfunction "2_2") (pintype "passive"))
      (node (ref "D17") (pin "2") (pinfunction "2_2") (pintype "passive"))
      (node (ref "IC5") (pin "8") (pinfunction "VCC_8") (pintype "passive"))
      (node (ref "Q4") (pin "2") (pinfunction "D_2") (pintype "passive"))
      (node (ref "Q5") (pin "2") (pinfunction "D_2") (pintype "passive"))
      (node (ref "R19") (pin "1") (pinfunction "1_1") (pintype "passive"))
      (node (ref "R21") (pin "1") (pinfunction "1_1") (pintype "passive"))
      (node (ref "R26") (pin "2") (pinfunction "2_2") (pintype "passive"))
      (node (ref "R35") (pin "2") (pinfunction "2_2") (pintype "passive"))
      (node (ref "R40") (pin "2") (pinfunction "2_2") (pintype "passive"))
      (node (ref "R51") (pin "2") (pinfunction "2_2") (pintype "passive"))
      (node (ref "SW1") (pin "2") (pinfunction "2_2") (pintype "passive"))
    )
    (net (code "45") (name "unconnected-(J5-Pad11)") (class "Default")
      (node (ref "J5") (pin "11") (pinfunction "11_11") (pintype "passive+no_connect"))
    )
  )
)
